# sd.net
KiCad netlist of a schematic drawn in EAGLE
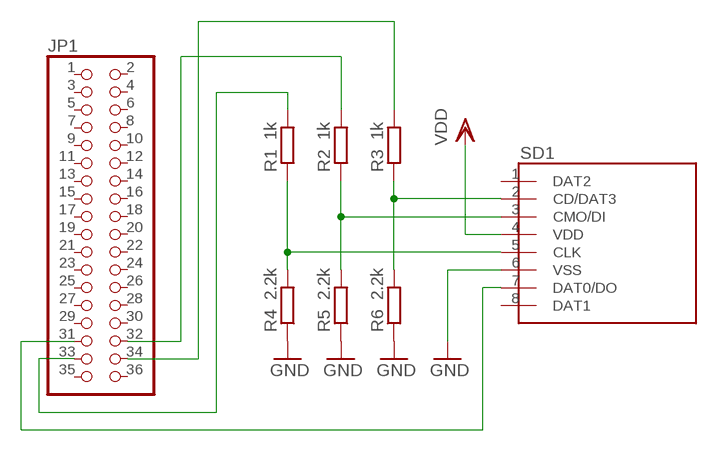
[diagram p0: schematic, sheet 1]

(export (version "E")
  (design (tool "Eeschema 10.0.6"))
  (components
    (comp (ref "JP1")
      (value "PINHD-2X18")
      (footprint "eagle-import:2X18")
      (libsource (lib "eagle-import") (part "PINHD-2X18"))
    )
    (comp (ref "R1")
      (value "1k")
      (footprint "eagle-import:0204V")
      (libsource (lib "eagle-import") (part "R-EU_0204/2V"))
    )
    (comp (ref "R2")
      (value "1k")
      (footprint "eagle-import:0204V")
      (libsource (lib "eagle-import") (part "R-EU_0204/2V"))
    )
    (comp (ref "R3")
      (value "1k")
      (footprint "eagle-import:0204V")
      (libsource (lib "eagle-import") (part "R-EU_0204/2V"))
    )
    (comp (ref "R4")
      (value "2.2k")
      (footprint "eagle-import:0204V")
      (libsource (lib "eagle-import") (part "R-EU_0204/2V"))
    )
    (comp (ref "R5")
      (value "2.2k")
      (footprint "eagle-import:0204V")
      (libsource (lib "eagle-import") (part "R-EU_0204/2V"))
    )
    (comp (ref "R6")
      (value "2.2k")
      (footprint "eagle-import:0204V")
      (libsource (lib "eagle-import") (part "R-EU_0204/2V"))
    )
    (comp (ref "SD1")
      (value "CK-40")
      (footprint "eagle-import:SD")
      (libsource (lib "eagle-import") (part "CK-40"))
    )
  )
  (nets
    (net (code "1") (name "GND") (class "Default")
      (node (ref "R4") (pin "1") (pinfunction "1_1") (pintype "passive"))
      (node (ref "R5") (pin "1") (pinfunction "1_1") (pintype "passive"))
      (node (ref "R6") (pin "1") (pinfunction "1_1") (pintype "passive"))
      (node (ref "SD1") (pin "6") (pinfunction "VSS_6") (pintype "bidirectional"))
    )
    (net (code "2") (name "Net-(JP1-Pad32)") (class "Default")
      (node (ref "JP1") (pin "32") (pinfunction "32_32") (pintype "passive"))
      (node (ref "R2") (pin "2") (pinfunction "2_2") (pintype "passive"))
    )
    (net (code "3") (name "Net-(JP1-Pad33)") (class "Default")
      (node (ref "JP1") (pin "33") (pinfunction "33_33") (pintype "passive"))
      (node (ref "R1") (pin "2") (pinfunction "2_2") (pintype "passive"))
    )
    (net (code "4") (name "Net-(JP1-Pad34)") (class "Default")
      (node (ref "JP1") (pin "34") (pinfunction "34_34") (pintype "passive"))
      (node (ref "R3") (pin "2") (pinfunction "2_2") (pintype "passive"))
    )
    (net (code "5") (name "Net-(SD1-CD{slash}DAT3)") (class "Default")
      (node (ref "R3") (pin "1") (pinfunction "1_1") (pintype "passive"))
      (node (ref "R6") (pin "2") (pinfunction "2_2") (pintype "passive"))
      (node (ref "SD1") (pin "2") (pinfunction "CD/DAT3_2") (pintype "bidirectional"))
    )
    (net (code "6") (name "Net-(SD1-CLK)") (class "Default")
      (node (ref "R1") (pin "1") (pinfunction "1_1") (pintype "passive"))
      (node (ref "R4") (pin "2") (pinfunction "2_2") (pintype "passive"))
      (node (ref "SD1") (pin "5") (pinfunction "CLK_5") (pintype "bidirectional"))
    )
    (net (code "7") (name "Net-(SD1-CMO{slash}DI)") (class "Default")
      (node (ref "R2") (pin "1") (pinfunction "1_1") (pintype "passive"))
      (node (ref "R5") (pin "2") (pinfunction "2_2") (pintype "passive"))
      (node (ref "SD1") (pin "3") (pinfunction "CMO/DI_3") (pintype "bidirectional"))
    )
    (net (code "8") (name "Net-(SD1-DAT0{slash}DO)") (class "Default")
      (node (ref "JP1") (pin "31") (pinfunction "31_31") (pintype "passive"))
      (node (ref "SD1") (pin "7") (pinfunction "DAT0/DO_7") (pintype "bidirectional"))
    )
    (net (code "9") (name "VDD") (class "Default")
      (node (ref "SD1") (pin "4") (pinfunction "VDD_4") (pintype "bidirectional"))
    )
    (net (code "10") (name "unconnected-(JP1-Pad1)") (class "Default")
      (node (ref "JP1") (pin "1") (pinfunction "1_1") (pintype "passive"))
    )
    (net (code "11") (name "unconnected-(JP1-Pad2)") (class "Default")
      (node (ref "JP1") (pin "2") (pinfunction "2_2") (pintype "passive"))
    )
    (net (code "12") (name "unconnected-(JP1-Pad3)") (class "Default")
      (node (ref "JP1") (pin "3") (pinfunction "3_3") (pintype "passive"))
    )
    (net (code "13") (name "unconnected-(JP1-Pad4)") (class "Default")
      (node (ref "JP1") (pin "4") (pinfunction "4_4") (pintype "passive"))
    )
    (net (code "14") (name "unconnected-(JP1-Pad5)") (class "Default")
      (node (ref "JP1") (pin "5") (pinfunction "5_5") (pintype "passive"))
    )
    (net (code "15") (name "unconnected-(JP1-Pad6)") (class "Default")
      (node (ref "JP1") (pin "6") (pinfunction "6_6") (pintype "passive"))
    )
    (net (code "16") (name "unconnected-(JP1-Pad7)") (class "Default")
      (node (ref "JP1") (pin "7") (pinfunction "7_7") (pintype "passive"))
    )
    (net (code "17") (name "unconnected-(JP1-Pad8)") (class "Default")
      (node (ref "JP1") (pin "8") (pinfunction "8_8") (pintype "passive"))
    )
    (net (code "18") (name "unconnected-(JP1-Pad9)") (class "Default")
      (node (ref "JP1") (pin "9") (pinfunction "9_9") (pintype "passive"))
    )
    (net (code "19") (name "unconnected-(JP1-Pad10)") (class "Default")
      (node (ref "JP1") (pin "10") (pinfunction "10_10") (pintype "passive"))
    )
    (net (code "20") (name "unconnected-(JP1-Pad11)") (class "Default")
      (node (ref "JP1") (pin "11") (pinfunction "11_11") (pintype "passive"))
    )
    (net (code "21") (name "unconnected-(JP1-Pad12)") (class "Default")
      (node (ref "JP1") (pin "12") (pinfunction "12_12") (pintype "passive"))
    )
    (net (code "22") (name "unconnected-(JP1-Pad13)") (class "Default")
      (node (ref "JP1") (pin "13") (pinfunction "13_13") (pintype "passive"))
    )
    (net (code "23") (name "unconnected-(JP1-Pad14)") (class "Default")
      (node (ref "JP1") (pin "14") (pinfunction "14_14") (pintype "passive"))
    )
    (net (code "24") (name "unconnected-(JP1-Pad15)") (class "Default")
      (node (ref "JP1") (pin "15") (pinfunction "15_15") (pintype "passive"))
    )
    (net (code "25") (name "unconnected-(JP1-Pad16)") (class "Default")
      (node (ref "JP1") (pin "16") (pinfunction "16_16") (pintype "passive"))
    )
    (net (code "26") (name "unconnected-(JP1-Pad17)") (class "Default")
      (node (ref "JP1") (pin "17") (pinfunction "17_17") (pintype "passive"))
    )
    (net (code "27") (name "unconnected-(JP1-Pad18)") (class "Default")
      (node (ref "JP1") (pin "18") (pinfunction "18_18") (pintype "passive"))
    )
    (net (code "28") (name "unconnected-(JP1-Pad19)") (class "Default")
      (node (ref "JP1") (pin "19") (pinfunction "19_19") (pintype "passive"))
    )
    (net (code "29") (name "unconnected-(JP1-Pad20)") (class "Default")
      (node (ref "JP1") (pin "20") (pinfunction "20_20") (pintype "passive"))
    )
    (net (code "30") (name "unconnected-(JP1-Pad21)") (class "Default")
      (node (ref "JP1") (pin "21") (pinfunction "21_21") (pintype "passive"))
    )
    (net (code "31") (name "unconnected-(JP1-Pad22)") (class "Default")
      (node (ref "JP1") (pin "22") (pinfunction "22_22") (pintype "passive"))
    )
    (net (code "32") (name "unconnected-(JP1-Pad23)") (class "Default")
      (node (ref "JP1") (pin "23") (pinfunction "23_23") (pintype "passive"))
    )
    (net (code "33") (name "unconnected-(JP1-Pad24)") (class "Default")
      (node (ref "JP1") (pin "24") (pinfunction "24_24") (pintype "passive"))
    )
    (net (code "34") (name "unconnected-(JP1-Pad25)") (class "Default")
      (node (ref "JP1") (pin "25") (pinfunction "25_25") (pintype "passive"))
    )
    (net (code "35") (name "unconnected-(JP1-Pad26)") (class "Default")
      (node (ref "JP1") (pin "26") (pinfunction "26_26") (pintype "passive"))
    )
    (net (code "36") (name "unconnected-(JP1-Pad27)") (class "Default")
      (node (ref "JP1") (pin "27") (pinfunction "27_27") (pintype "passive"))
    )
    (net (code "37") (name "unconnected-(JP1-Pad28)") (class "Default")
      (node (ref "JP1") (pin "28") (pinfunction "28_28") (pintype "passive"))
    )
    (net (code "38") (name "unconnected-(JP1-Pad29)") (class "Default")
      (node (ref "JP1") (pin "29") (pinfunction "29_29") (pintype "passive"))
    )
    (net (code "39") (name "unconnected-(JP1-Pad30)") (class "Default")
      (node (ref "JP1") (pin "30") (pinfunction "30_30") (pintype "passive"))
    )
    (net (code "40") (name "unconnected-(JP1-Pad35)") (class "Default")
      (node (ref "JP1") (pin "35") (pinfunction "35_35") (pintype "passive"))
    )
    (net (code "41") (name "unconnected-(JP1-Pad36)") (class "Default")
      (node (ref "JP1") (pin "36") (pinfunction "36_36") (pintype "passive"))
    )
    (net (code "42") (name "unconnected-(SD1-DAT1-Pad8)") (class "Default")
      (node (ref "SD1") (pin "8") (pinfunction "DAT1_8") (pintype "bidirectional"))
    )
    (net (code "43") (name "unconnected-(SD1-DAT2-Pad1)") (class "Default")
      (node (ref "SD1") (pin "1") (pinfunction "DAT2_1") (pintype "bidirectional"))
    )
  )
)
